# ESP_Irrigation.net
KiCad netlist of a schematic drawn in EAGLE
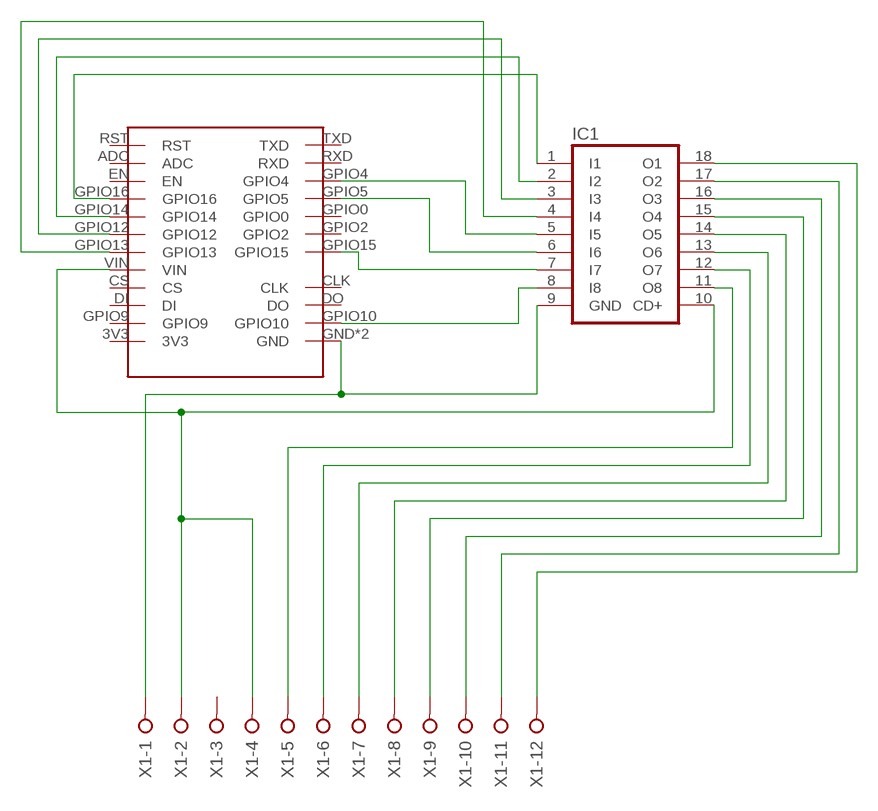
[diagram p0: schematic, sheet 1]

(export (version "E")
  (design (tool "Eeschema 10.0.6"))
  (components
    (comp (ref "IC1")
      (value "ULN2803A")
      (footprint "eagle-import:DIL18")
      (libsource (lib "eagle-import") (part "ULN2803A"))
    )
    (comp (ref "U$1")
      (value "ESP12ADAPTERBOARD")
      (footprint "eagle-import:ESP12ADAPTERBOARD")
      (libsource (lib "eagle-import") (part "ESP12ADAPTERBOARD"))
    )
    (comp (ref "X1")
      (value "W237-12P")
      (footprint "eagle-import:W237-12P")
      (libsource (lib "eagle-import") (part "W237-12P"))
    )
  )
  (nets
    (net (code "1") (name "Net-(IC1-CD+)") (class "Default")
      (node (ref "IC1") (pin "10") (pinfunction "CD+_10") (pintype "passive"))
      (node (ref "U$1") (pin "VIN") (pinfunction "VIN_VIN") (pintype "bidirectional"))
      (node (ref "X1") (pin "2") (pinfunction "KL_2") (pintype "passive"))
      (node (ref "X1") (pin "4") (pinfunction "KL_4") (pintype "passive"))
    )
    (net (code "2") (name "Net-(IC1-GND)") (class "Default")
      (node (ref "IC1") (pin "9") (pinfunction "GND_9") (pintype "power_in"))
      (node (ref "U$1") (pin "GND") (pinfunction "GND_GND") (pintype "bidirectional"))
      (node (ref "U$1") (pin "GND1") (pinfunction "GND_GND1") (pintype "bidirectional"))
      (node (ref "X1") (pin "1") (pinfunction "KL_1") (pintype "passive"))
    )
    (net (code "3") (name "Net-(IC1-I1)") (class "Default")
      (node (ref "IC1") (pin "1") (pinfunction "I1_1") (pintype "input"))
      (node (ref "U$1") (pin "GPIO16") (pinfunction "GPIO16_GPIO16") (pintype "bidirectional"))
    )
    (net (code "4") (name "Net-(IC1-I2)") (class "Default")
      (node (ref "IC1") (pin "2") (pinfunction "I2_2") (pintype "input"))
      (node (ref "U$1") (pin "GPIO14") (pinfunction "GPIO14_GPIO14") (pintype "bidirectional"))
    )
    (net (code "5") (name "Net-(IC1-I3)") (class "Default")
      (node (ref "IC1") (pin "3") (pinfunction "I3_3") (pintype "input"))
      (node (ref "U$1") (pin "GPIO12") (pinfunction "GPIO12_GPIO12") (pintype "bidirectional"))
    )
    (net (code "6") (name "Net-(IC1-I4)") (class "Default")
      (node (ref "IC1") (pin "4") (pinfunction "I4_4") (pintype "input"))
      (node (ref "U$1") (pin "GPIO13") (pinfunction "GPIO13_GPIO13") (pintype "bidirectional"))
    )
    (net (code "7") (name "Net-(IC1-I5)") (class "Default")
      (node (ref "IC1") (pin "5") (pinfunction "I5_5") (pintype "input"))
      (node (ref "U$1") (pin "GPIO4") (pinfunction "GPIO4_GPIO4") (pintype "bidirectional"))
    )
    (net (code "8") (name "Net-(IC1-I6)") (class "Default")
      (node (ref "IC1") (pin "6") (pinfunction "I6_6") (pintype "input"))
      (node (ref "U$1") (pin "GPIO5") (pinfunction "GPIO5_GPIO5") (pintype "bidirectional"))
    )
    (net (code "9") (name "Net-(IC1-I7)") (class "Default")
      (node (ref "IC1") (pin "7") (pinfunction "I7_7") (pintype "input"))
      (node (ref "U$1") (pin "GPIO15") (pinfunction "GPIO15_GPIO15") (pintype "bidirectional"))
    )
    (net (code "10") (name "Net-(IC1-I8)") (class "Default")
      (node (ref "IC1") (pin "8") (pinfunction "I8_8") (pintype "input"))
      (node (ref "U$1") (pin "GPIO10") (pinfunction "GPIO10_GPIO10") (pintype "bidirectional"))
    )
    (net (code "11") (name "Net-(IC1-O1)") (class "Default")
      (node (ref "IC1") (pin "18") (pinfunction "O1_18") (pintype "open_collector"))
      (node (ref "X1") (pin "12") (pinfunction "KL_12") (pintype "passive"))
    )
    (net (code "12") (name "Net-(IC1-O2)") (class "Default")
      (node (ref "IC1") (pin "17") (pinfunction "O2_17") (pintype "open_collector"))
      (node (ref "X1") (pin "11") (pinfunction "KL_11") (pintype "passive"))
    )
    (net (code "13") (name "Net-(IC1-O3)") (class "Default")
      (node (ref "IC1") (pin "16") (pinfunction "O3_16") (pintype "open_collector"))
      (node (ref "X1") (pin "10") (pinfunction "KL_10") (pintype "passive"))
    )
    (net (code "14") (name "Net-(IC1-O4)") (class "Default")
      (node (ref "IC1") (pin "15") (pinfunction "O4_15") (pintype "open_collector"))
      (node (ref "X1") (pin "9") (pinfunction "KL_9") (pintype "passive"))
    )
    (net (code "15") (name "Net-(IC1-O5)") (class "Default")
      (node (ref "IC1") (pin "14") (pinfunction "O5_14") (pintype "open_collector"))
      (node (ref "X1") (pin "8") (pinfunction "KL_8") (pintype "passive"))
    )
    (net (code "16") (name "Net-(IC1-O6)") (class "Default")
      (node (ref "IC1") (pin "13") (pinfunction "O6_13") (pintype "open_collector"))
      (node (ref "X1") (pin "7") (pinfunction "KL_7") (pintype "passive"))
    )
    (net (code "17") (name "Net-(IC1-O7)") (class "Default")
      (node (ref "IC1") (pin "12") (pinfunction "O7_12") (pintype "open_collector"))
      (node (ref "X1") (pin "6") (pinfunction "KL_6") (pintype "passive"))
    )
    (net (code "18") (name "Net-(IC1-O8)") (class "Default")
      (node (ref "IC1") (pin "11") (pinfunction "O8_11") (pintype "open_collector"))
      (node (ref "X1") (pin "5") (pinfunction "KL_5") (pintype "passive"))
    )
    (net (code "19") (name "unconnected-(U$1-Pad3V3)") (class "Default")
      (node (ref "U$1") (pin "3V3") (pinfunction "3V3_3V3") (pintype "bidirectional"))
    )
    (net (code "20") (name "unconnected-(U$1-PadADC)") (class "Default")
      (node (ref "U$1") (pin "ADC") (pinfunction "ADC_ADC") (pintype "bidirectional"))
    )
    (net (code "21") (name "unconnected-(U$1-PadCLK)") (class "Default")
      (node (ref "U$1") (pin "CLK") (pinfunction "CLK_CLK") (pintype "bidirectional"))
    )
    (net (code "22") (name "unconnected-(U$1-PadCS)") (class "Default")
      (node (ref "U$1") (pin "CS") (pinfunction "CS_CS") (pintype "bidirectional"))
    )
    (net (code "23") (name "unconnected-(U$1-PadDI)") (class "Default")
      (node (ref "U$1") (pin "DI") (pinfunction "DI_DI") (pintype "bidirectional"))
    )
    (net (code "24") (name "unconnected-(U$1-PadDO)") (class "Default")
      (node (ref "U$1") (pin "DO") (pinfunction "DO_DO") (pintype "bidirectional"))
    )
    (net (code "25") (name "unconnected-(U$1-PadEN)") (class "Default")
      (node (ref "U$1") (pin "EN") (pinfunction "EN_EN") (pintype "bidirectional"))
    )
    (net (code "26") (name "unconnected-(U$1-PadGPIO0)") (class "Default")
      (node (ref "U$1") (pin "GPIO0") (pinfunction "GPIO0_GPIO0") (pintype "bidirectional"))
    )
    (net (code "27") (name "unconnected-(U$1-PadGPIO2)") (class "Default")
      (node (ref "U$1") (pin "GPIO2") (pinfunction "GPIO2_GPIO2") (pintype "bidirectional"))
    )
    (net (code "28") (name "unconnected-(U$1-PadGPIO9)") (class "Default")
      (node (ref "U$1") (pin "GPIO9") (pinfunction "GPIO9_GPIO9") (pintype "bidirectional"))
    )
    (net (code "29") (name "unconnected-(U$1-PadRST)") (class "Default")
      (node (ref "U$1") (pin "RST") (pinfunction "RST_RST") (pintype "bidirectional"))
    )
    (net (code "30") (name "unconnected-(U$1-PadRXD)") (class "Default")
      (node (ref "U$1") (pin "RXD") (pinfunction "RXD_RXD") (pintype "bidirectional"))
    )
    (net (code "31") (name "unconnected-(U$1-PadTXD)") (class "Default")
      (node (ref "U$1") (pin "TXD") (pinfunction "TXD_TXD") (pintype "bidirectional"))
    )
    (net (code "32") (name "unconnected-(X1F-KL-Pad3)") (class "Default")
      (node (ref "X1") (pin "3") (pinfunction "KL_3") (pintype "passive"))
    )
  )
)
